# ClockDivider.net
KiCad netlist of a schematic drawn in Altium Designer
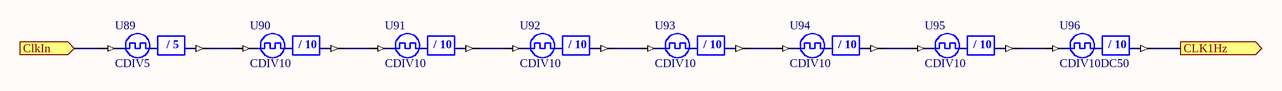
[diagram p0: ClockDivider.SchDoc]

(export (version "E")
  (design (tool "Eeschema 10.0.6"))
  (components
    (comp (ref "U89")
      (value "CDIV5")
      (description "Clock Divider by 5")
      (fields (field (name "PUBLISHER") "Altium Limited"))
      (libsource (lib "FPGA Generic") (part "CDIV5"))
    )
    (comp (ref "U90")
      (value "CDIV10")
      (description "Clock Divider by 10")
      (fields (field (name "PUBLISHER") "Altium Limited"))
      (libsource (lib "FPGA Generic") (part "CDIV10"))
    )
    (comp (ref "U91")
      (value "CDIV10")
      (description "Clock Divider by 10")
      (fields (field (name "PUBLISHER") "Altium Limited"))
      (libsource (lib "FPGA Generic") (part "CDIV10"))
    )
    (comp (ref "U92")
      (value "CDIV10")
      (description "Clock Divider by 10")
      (fields (field (name "PUBLISHER") "Altium Limited"))
      (libsource (lib "FPGA Generic") (part "CDIV10"))
    )
    (comp (ref "U93")
      (value "CDIV10")
      (description "Clock Divider by 10")
      (fields (field (name "PUBLISHER") "Altium Limited"))
      (libsource (lib "FPGA Generic") (part "CDIV10"))
    )
    (comp (ref "U94")
      (value "CDIV10")
      (description "Clock Divider by 10")
      (fields (field (name "PUBLISHER") "Altium Limited"))
      (libsource (lib "FPGA Generic") (part "CDIV10"))
    )
    (comp (ref "U95")
      (value "CDIV10")
      (description "Clock Divider by 10")
      (fields (field (name "PUBLISHER") "Altium Limited"))
      (libsource (lib "FPGA Generic") (part "CDIV10"))
    )
    (comp (ref "U96")
      (value "CDIV10DC50")
      (description "Clock Divider by 10 with 50% Duty Cycle Output")
      (fields (field (name "PUBLISHER") "Altium Limited"))
      (libsource (lib "FPGA Generic") (part "CDIV10DC50"))
    )
  )
  (nets
    (net (code "1") (name "/CLK1Hz") (class "Default")
      (node (ref "U96") (pin "CLKDV") (pinfunction "CLKDV_CLKDV") (pintype "output"))
    )
    (net (code "2") (name "/ClkIn") (class "Default")
      (node (ref "U89") (pin "CLKIN") (pinfunction "CLKIN_CLKIN") (pintype "input"))
    )
    (net (code "3") (name "Net-(U89-PadCLKDV)") (class "Default")
      (node (ref "U89") (pin "CLKDV") (pinfunction "CLKDV_CLKDV") (pintype "output"))
      (node (ref "U90") (pin "CLKIN") (pinfunction "CLKIN_CLKIN") (pintype "input"))
    )
    (net (code "4") (name "Net-(U90-PadCLKDV)") (class "Default")
      (node (ref "U90") (pin "CLKDV") (pinfunction "CLKDV_CLKDV") (pintype "output"))
      (node (ref "U91") (pin "CLKIN") (pinfunction "CLKIN_CLKIN") (pintype "input"))
    )
    (net (code "5") (name "Net-(U91-PadCLKDV)") (class "Default")
      (node (ref "U91") (pin "CLKDV") (pinfunction "CLKDV_CLKDV") (pintype "output"))
      (node (ref "U92") (pin "CLKIN") (pinfunction "CLKIN_CLKIN") (pintype "input"))
    )
    (net (code "6") (name "Net-(U92-PadCLKDV)") (class "Default")
      (node (ref "U92") (pin "CLKDV") (pinfunction "CLKDV_CLKDV") (pintype "output"))
      (node (ref "U93") (pin "CLKIN") (pinfunction "CLKIN_CLKIN") (pintype "input"))
    )
    (net (code "7") (name "Net-(U93-PadCLKDV)") (class "Default")
      (node (ref "U93") (pin "CLKDV") (pinfunction "CLKDV_CLKDV") (pintype "output"))
      (node (ref "U94") (pin "CLKIN") (pinfunction "CLKIN_CLKIN") (pintype "input"))
    )
    (net (code "8") (name "Net-(U94-PadCLKDV)") (class "Default")
      (node (ref "U94") (pin "CLKDV") (pinfunction "CLKDV_CLKDV") (pintype "output"))
      (node (ref "U95") (pin "CLKIN") (pinfunction "CLKIN_CLKIN") (pintype "input"))
    )
    (net (code "9") (name "Net-(U95-PadCLKDV)") (class "Default")
      (node (ref "U95") (pin "CLKDV") (pinfunction "CLKDV_CLKDV") (pintype "output"))
      (node (ref "U96") (pin "CLKIN") (pinfunction "CLKIN_CLKIN") (pintype "input"))
    )
  )
)
